# keyboard.net
KiCad netlist of a schematic drawn in EAGLE
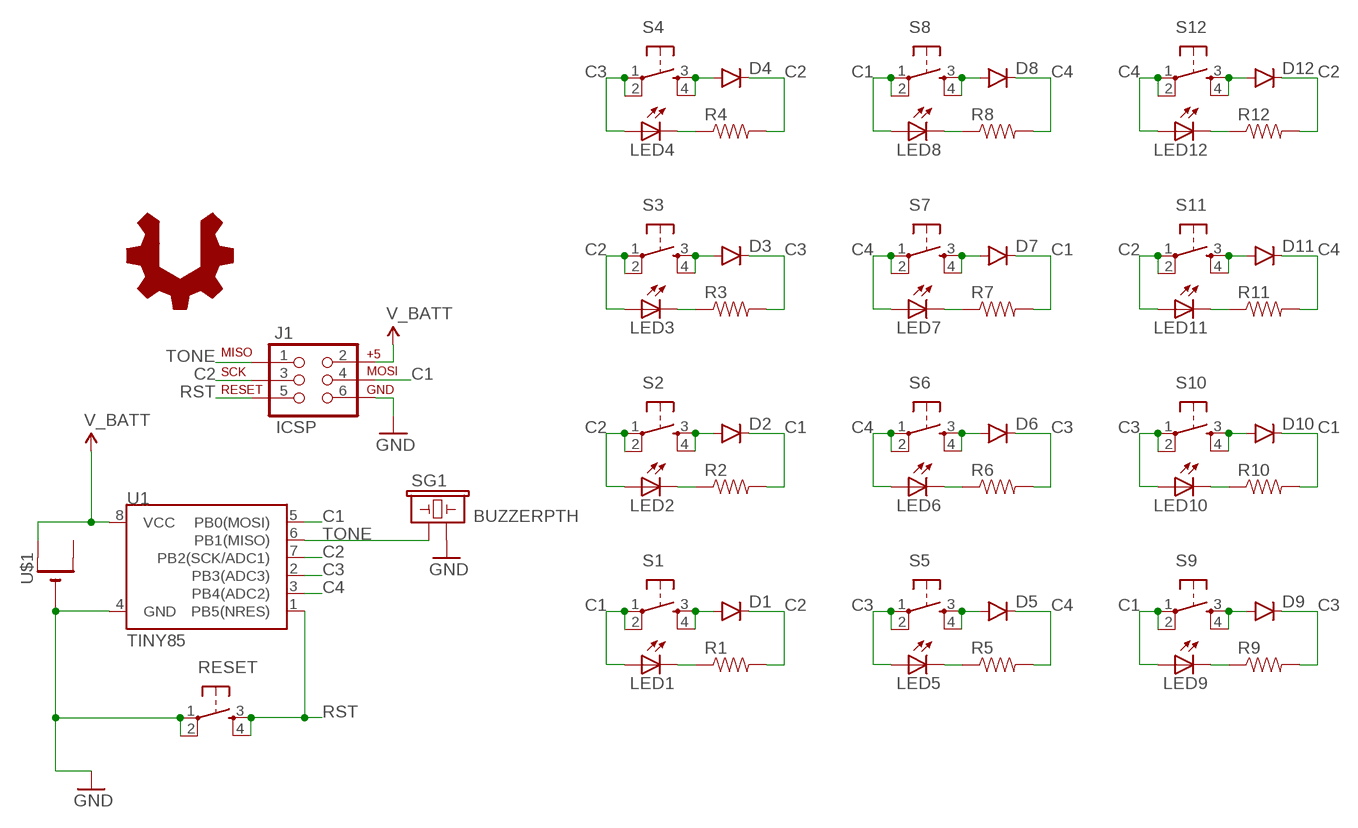
[diagram p0: schematic, sheet 1]

(export (version "E")
  (design (tool "Eeschema 10.0.6"))
  (components
    (comp (ref "D1")
      (value "DIODE1N4148")
      (footprint "eagle-import:DIODE-1N4148")
      (libsource (lib "eagle-import") (part "DIODE1N4148"))
    )
    (comp (ref "D2")
      (value "DIODE1N4148")
      (footprint "eagle-import:DIODE-1N4148")
      (libsource (lib "eagle-import") (part "DIODE1N4148"))
    )
    (comp (ref "D3")
      (value "DIODE1N4148")
      (footprint "eagle-import:DIODE-1N4148")
      (libsource (lib "eagle-import") (part "DIODE1N4148"))
    )
    (comp (ref "D4")
      (value "DIODE1N4148")
      (footprint "eagle-import:DIODE-1N4148")
      (libsource (lib "eagle-import") (part "DIODE1N4148"))
    )
    (comp (ref "D5")
      (value "DIODE1N4148")
      (footprint "eagle-import:DIODE-1N4148")
      (libsource (lib "eagle-import") (part "DIODE1N4148"))
    )
    (comp (ref "D6")
      (value "DIODE1N4148")
      (footprint "eagle-import:DIODE-1N4148")
      (libsource (lib "eagle-import") (part "DIODE1N4148"))
    )
    (comp (ref "D7")
      (value "DIODE1N4148")
      (footprint "eagle-import:DIODE-1N4148")
      (libsource (lib "eagle-import") (part "DIODE1N4148"))
    )
    (comp (ref "D8")
      (value "DIODE1N4148")
      (footprint "eagle-import:DIODE-1N4148")
      (libsource (lib "eagle-import") (part "DIODE1N4148"))
    )
    (comp (ref "D9")
      (value "DIODE1N4148")
      (footprint "eagle-import:DIODE-1N4148")
      (libsource (lib "eagle-import") (part "DIODE1N4148"))
    )
    (comp (ref "D10")
      (value "DIODE1N4148")
      (footprint "eagle-import:DIODE-1N4148")
      (libsource (lib "eagle-import") (part "DIODE1N4148"))
    )
    (comp (ref "D11")
      (value "DIODE1N4148")
      (footprint "eagle-import:DIODE-1N4148")
      (libsource (lib "eagle-import") (part "DIODE1N4148"))
    )
    (comp (ref "D12")
      (value "DIODE1N4148")
      (footprint "eagle-import:DIODE-1N4148")
      (libsource (lib "eagle-import") (part "DIODE1N4148"))
    )
    (comp (ref "J1")
      (value "ICSP")
      (footprint "eagle-import:2X3-NS")
      (libsource (lib "eagle-import") (part "AVR_SPI_PRG_6LABELED"))
    )
    (comp (ref "LED1")
      (value "LED5MM")
      (footprint "eagle-import:LED5MM")
      (libsource (lib "eagle-import") (part "LED5MM"))
    )
    (comp (ref "LED2")
      (value "LED5MM")
      (footprint "eagle-import:LED5MM")
      (libsource (lib "eagle-import") (part "LED5MM"))
    )
    (comp (ref "LED3")
      (value "LED5MM")
      (footprint "eagle-import:LED5MM")
      (libsource (lib "eagle-import") (part "LED5MM"))
    )
    (comp (ref "LED4")
      (value "LED5MM")
      (footprint "eagle-import:LED5MM")
      (libsource (lib "eagle-import") (part "LED5MM"))
    )
    (comp (ref "LED5")
      (value "LED5MM")
      (footprint "eagle-import:LED5MM")
      (libsource (lib "eagle-import") (part "LED5MM"))
    )
    (comp (ref "LED6")
      (value "LED5MM")
      (footprint "eagle-import:LED5MM")
      (libsource (lib "eagle-import") (part "LED5MM"))
    )
    (comp (ref "LED7")
      (value "LED5MM")
      (footprint "eagle-import:LED5MM")
      (libsource (lib "eagle-import") (part "LED5MM"))
    )
    (comp (ref "LED8")
      (value "LED5MM")
      (footprint "eagle-import:LED5MM")
      (libsource (lib "eagle-import") (part "LED5MM"))
    )
    (comp (ref "LED9")
      (value "LED5MM")
      (footprint "eagle-import:LED5MM")
      (libsource (lib "eagle-import") (part "LED5MM"))
    )
    (comp (ref "LED10")
      (value "LED5MM")
      (footprint "eagle-import:LED5MM")
      (libsource (lib "eagle-import") (part "LED5MM"))
    )
    (comp (ref "LED11")
      (value "LED5MM")
      (footprint "eagle-import:LED5MM")
      (libsource (lib "eagle-import") (part "LED5MM"))
    )
    (comp (ref "LED12")
      (value "LED5MM")
      (footprint "eagle-import:LED5MM")
      (libsource (lib "eagle-import") (part "LED5MM"))
    )
    (comp (ref "R1")
      (value "RESISTORAXIAL-0.3")
      (footprint "eagle-import:AXIAL-0.3")
      (libsource (lib "eagle-import") (part "RESISTORAXIAL-0.3"))
    )
    (comp (ref "R2")
      (value "RESISTORAXIAL-0.3")
      (footprint "eagle-import:AXIAL-0.3")
      (libsource (lib "eagle-import") (part "RESISTORAXIAL-0.3"))
    )
    (comp (ref "R3")
      (value "RESISTORAXIAL-0.3")
      (footprint "eagle-import:AXIAL-0.3")
      (libsource (lib "eagle-import") (part "RESISTORAXIAL-0.3"))
    )
    (comp (ref "R4")
      (value "RESISTORAXIAL-0.3")
      (footprint "eagle-import:AXIAL-0.3")
      (libsource (lib "eagle-import") (part "RESISTORAXIAL-0.3"))
    )
    (comp (ref "R5")
      (value "RESISTORAXIAL-0.3")
      (footprint "eagle-import:AXIAL-0.3")
      (libsource (lib "eagle-import") (part "RESISTORAXIAL-0.3"))
    )
    (comp (ref "R6")
      (value "RESISTORAXIAL-0.3")
      (footprint "eagle-import:AXIAL-0.3")
      (libsource (lib "eagle-import") (part "RESISTORAXIAL-0.3"))
    )
    (comp (ref "R7")
      (value "RESISTORAXIAL-0.3")
      (footprint "eagle-import:AXIAL-0.3")
      (libsource (lib "eagle-import") (part "RESISTORAXIAL-0.3"))
    )
    (comp (ref "R8")
      (value "RESISTORAXIAL-0.3")
      (footprint "eagle-import:AXIAL-0.3")
      (libsource (lib "eagle-import") (part "RESISTORAXIAL-0.3"))
    )
    (comp (ref "R9")
      (value "RESISTORAXIAL-0.3")
      (footprint "eagle-import:AXIAL-0.3")
      (libsource (lib "eagle-import") (part "RESISTORAXIAL-0.3"))
    )
    (comp (ref "R10")
      (value "RESISTORAXIAL-0.3")
      (footprint "eagle-import:AXIAL-0.3")
      (libsource (lib "eagle-import") (part "RESISTORAXIAL-0.3"))
    )
    (comp (ref "R11")
      (value "RESISTORAXIAL-0.3")
      (footprint "eagle-import:AXIAL-0.3")
      (libsource (lib "eagle-import") (part "RESISTORAXIAL-0.3"))
    )
    (comp (ref "R12")
      (value "RESISTORAXIAL-0.3")
      (footprint "eagle-import:AXIAL-0.3")
      (libsource (lib "eagle-import") (part "RESISTORAXIAL-0.3"))
    )
    (comp (ref "RESET")
      (value "TAC_SWITCHPTH")
      (footprint "eagle-import:TACTILE-PTH")
      (libsource (lib "eagle-import") (part "TAC_SWITCHPTH"))
    )
    (comp (ref "S1")
      (value "TAC_SWITCHPTH")
      (footprint "eagle-import:TACTILE-PTH")
      (libsource (lib "eagle-import") (part "TAC_SWITCHPTH"))
    )
    (comp (ref "S2")
      (value "TAC_SWITCHPTH")
      (footprint "eagle-import:TACTILE-PTH")
      (libsource (lib "eagle-import") (part "TAC_SWITCHPTH"))
    )
    (comp (ref "S3")
      (value "TAC_SWITCHPTH")
      (footprint "eagle-import:TACTILE-PTH")
      (libsource (lib "eagle-import") (part "TAC_SWITCHPTH"))
    )
    (comp (ref "S4")
      (value "TAC_SWITCHPTH")
      (footprint "eagle-import:TACTILE-PTH")
      (libsource (lib "eagle-import") (part "TAC_SWITCHPTH"))
    )
    (comp (ref "S5")
      (value "TAC_SWITCHPTH")
      (footprint "eagle-import:TACTILE-PTH")
      (libsource (lib "eagle-import") (part "TAC_SWITCHPTH"))
    )
    (comp (ref "S6")
      (value "TAC_SWITCHPTH")
      (footprint "eagle-import:TACTILE-PTH")
      (libsource (lib "eagle-import") (part "TAC_SWITCHPTH"))
    )
    (comp (ref "S7")
      (value "TAC_SWITCHPTH")
      (footprint "eagle-import:TACTILE-PTH")
      (libsource (lib "eagle-import") (part "TAC_SWITCHPTH"))
    )
    (comp (ref "S8")
      (value "TAC_SWITCHPTH")
      (footprint "eagle-import:TACTILE-PTH")
      (libsource (lib "eagle-import") (part "TAC_SWITCHPTH"))
    )
    (comp (ref "S9")
      (value "TAC_SWITCHPTH")
      (footprint "eagle-import:TACTILE-PTH")
      (libsource (lib "eagle-import") (part "TAC_SWITCHPTH"))
    )
    (comp (ref "S10")
      (value "TAC_SWITCHPTH")
      (footprint "eagle-import:TACTILE-PTH")
      (libsource (lib "eagle-import") (part "TAC_SWITCHPTH"))
    )
    (comp (ref "S11")
      (value "TAC_SWITCHPTH")
      (footprint "eagle-import:TACTILE-PTH")
      (libsource (lib "eagle-import") (part "TAC_SWITCHPTH"))
    )
    (comp (ref "S12")
      (value "TAC_SWITCHPTH")
      (footprint "eagle-import:TACTILE-PTH")
      (libsource (lib "eagle-import") (part "TAC_SWITCHPTH"))
    )
    (comp (ref "SG1")
      (value "BUZZERPTH")
      (footprint "eagle-import:BUZZER-12MM")
      (libsource (lib "eagle-import") (part "BUZZERPTH"))
    )
    (comp (ref "U$1")
      (value "CR2032THM")
      (footprint "eagle-import:CR2032-THRU")
      (libsource (lib "eagle-import") (part "CR2032THM"))
    )
    (comp (ref "U$2")
      (value "USER_HACKABLE")
      (footprint "eagle-import:USER_HACKABLE")
      (libsource (lib "eagle-import") (part "USER_HACKABLE"))
    )
    (comp (ref "U1")
      (value "TINY85")
      (footprint "eagle-import:DIP08")
      (libsource (lib "eagle-import") (part "ATTINY45TINY85-20-DIP"))
    )
  )
  (nets
    (net (code "1") (name "/C1") (class "Default")
      (node (ref "D10") (pin "C") (pinfunction "C_C") (pintype "passive"))
      (node (ref "D2") (pin "C") (pinfunction "C_C") (pintype "passive"))
      (node (ref "D7") (pin "C") (pinfunction "C_C") (pintype "passive"))
      (node (ref "J1") (pin "4") (pinfunction "MOSI_4") (pintype "passive"))
      (node (ref "LED1") (pin "A") (pinfunction "A_A") (pintype "passive"))
      (node (ref "LED8") (pin "A") (pinfunction "A_A") (pintype "passive"))
      (node (ref "LED9") (pin "A") (pinfunction "A_A") (pintype "passive"))
      (node (ref "R10") (pin "P$2") (pinfunction "2_P$2") (pintype "passive"))
      (node (ref "R2") (pin "P$2") (pinfunction "2_P$2") (pintype "passive"))
      (node (ref "R7") (pin "P$2") (pinfunction "2_P$2") (pintype "passive"))
      (node (ref "S1") (pin "1") (pinfunction "1_1") (pintype "passive"))
      (node (ref "S1") (pin "2") (pinfunction "2_2") (pintype "passive"))
      (node (ref "S8") (pin "1") (pinfunction "1_1") (pintype "passive"))
      (node (ref "S8") (pin "2") (pinfunction "2_2") (pintype "passive"))
      (node (ref "S9") (pin "1") (pinfunction "1_1") (pintype "passive"))
      (node (ref "S9") (pin "2") (pinfunction "2_2") (pintype "passive"))
      (node (ref "U1") (pin "5") (pinfunction "PB0(MOSI)_5") (pintype "bidirectional"))
    )
    (net (code "2") (name "/C2") (class "Default")
      (node (ref "D1") (pin "C") (pinfunction "C_C") (pintype "passive"))
      (node (ref "D12") (pin "C") (pinfunction "C_C") (pintype "passive"))
      (node (ref "D4") (pin "C") (pinfunction "C_C") (pintype "passive"))
      (node (ref "J1") (pin "3") (pinfunction "SCK_3") (pintype "passive"))
      (node (ref "LED11") (pin "A") (pinfunction "A_A") (pintype "passive"))
      (node (ref "LED2") (pin "A") (pinfunction "A_A") (pintype "passive"))
      (node (ref "LED3") (pin "A") (pinfunction "A_A") (pintype "passive"))
      (node (ref "R1") (pin "P$2") (pinfunction "2_P$2") (pintype "passive"))
      (node (ref "R12") (pin "P$2") (pinfunction "2_P$2") (pintype "passive"))
      (node (ref "R4") (pin "P$2") (pinfunction "2_P$2") (pintype "passive"))
      (node (ref "S11") (pin "1") (pinfunction "1_1") (pintype "passive"))
      (node (ref "S11") (pin "2") (pinfunction "2_2") (pintype "passive"))
      (node (ref "S2") (pin "1") (pinfunction "1_1") (pintype "passive"))
      (node (ref "S2") (pin "2") (pinfunction "2_2") (pintype "passive"))
      (node (ref "S3") (pin "1") (pinfunction "1_1") (pintype "passive"))
      (node (ref "S3") (pin "2") (pinfunction "2_2") (pintype "passive"))
      (node (ref "U1") (pin "7") (pinfunction "PB2(SCK/ADC1)_7") (pintype "bidirectional"))
    )
    (net (code "3") (name "/C3") (class "Default")
      (node (ref "D3") (pin "C") (pinfunction "C_C") (pintype "passive"))
      (node (ref "D6") (pin "C") (pinfunction "C_C") (pintype "passive"))
      (node (ref "D9") (pin "C") (pinfunction "C_C") (pintype "passive"))
      (node (ref "LED10") (pin "A") (pinfunction "A_A") (pintype "passive"))
      (node (ref "LED4") (pin "A") (pinfunction "A_A") (pintype "passive"))
      (node (ref "LED5") (pin "A") (pinfunction "A_A") (pintype "passive"))
      (node (ref "R3") (pin "P$2") (pinfunction "2_P$2") (pintype "passive"))
      (node (ref "R6") (pin "P$2") (pinfunction "2_P$2") (pintype "passive"))
      (node (ref "R9") (pin "P$2") (pinfunction "2_P$2") (pintype "passive"))
      (node (ref "S10") (pin "1") (pinfunction "1_1") (pintype "passive"))
      (node (ref "S10") (pin "2") (pinfunction "2_2") (pintype "passive"))
      (node (ref "S4") (pin "1") (pinfunction "1_1") (pintype "passive"))
      (node (ref "S4") (pin "2") (pinfunction "2_2") (pintype "passive"))
      (node (ref "S5") (pin "1") (pinfunction "1_1") (pintype "passive"))
      (node (ref "S5") (pin "2") (pinfunction "2_2") (pintype "passive"))
      (node (ref "U1") (pin "2") (pinfunction "PB3(ADC3)_2") (pintype "bidirectional"))
    )
    (net (code "4") (name "/C4") (class "Default")
      (node (ref "D11") (pin "C") (pinfunction "C_C") (pintype "passive"))
      (node (ref "D5") (pin "C") (pinfunction "C_C") (pintype "passive"))
      (node (ref "D8") (pin "C") (pinfunction "C_C") (pintype "passive"))
      (node (ref "LED12") (pin "A") (pinfunction "A_A") (pintype "passive"))
      (node (ref "LED6") (pin "A") (pinfunction "A_A") (pintype "passive"))
      (node (ref "LED7") (pin "A") (pinfunction "A_A") (pintype "passive"))
      (node (ref "R11") (pin "P$2") (pinfunction "2_P$2") (pintype "passive"))
      (node (ref "R5") (pin "P$2") (pinfunction "2_P$2") (pintype "passive"))
      (node (ref "R8") (pin "P$2") (pinfunction "2_P$2") (pintype "passive"))
      (node (ref "S12") (pin "1") (pinfunction "1_1") (pintype "passive"))
      (node (ref "S12") (pin "2") (pinfunction "2_2") (pintype "passive"))
      (node (ref "S6") (pin "1") (pinfunction "1_1") (pintype "passive"))
      (node (ref "S6") (pin "2") (pinfunction "2_2") (pintype "passive"))
      (node (ref "S7") (pin "1") (pinfunction "1_1") (pintype "passive"))
      (node (ref "S7") (pin "2") (pinfunction "2_2") (pintype "passive"))
      (node (ref "U1") (pin "3") (pinfunction "PB4(ADC2)_3") (pintype "bidirectional"))
    )
    (net (code "5") (name "/RST") (class "Default")
      (node (ref "J1") (pin "5") (pinfunction "RST_5") (pintype "passive"))
      (node (ref "RESET") (pin "3") (pinfunction "3_3") (pintype "passive"))
      (node (ref "RESET") (pin "4") (pinfunction "4_4") (pintype "passive"))
      (node (ref "U1") (pin "1") (pinfunction "PB5(NRES)_1") (pintype "bidirectional"))
    )
    (net (code "6") (name "/TONE") (class "Default")
      (node (ref "J1") (pin "1") (pinfunction "MISO_1") (pintype "passive"))
      (node (ref "SG1") (pin "+") (pinfunction "1_+") (pintype "passive"))
      (node (ref "U1") (pin "6") (pinfunction "PB1(MISO)_6") (pintype "bidirectional"))
    )
    (net (code "7") (name "GND") (class "Default")
      (node (ref "J1") (pin "6") (pinfunction "GND_6") (pintype "passive"))
      (node (ref "RESET") (pin "1") (pinfunction "1_1") (pintype "passive"))
      (node (ref "RESET") (pin "2") (pinfunction "2_2") (pintype "passive"))
      (node (ref "SG1") (pin "-") (pinfunction "2_-") (pintype "passive"))
      (node (ref "U$1") (pin "-") (pinfunction "-_-") (pintype "passive"))
      (node (ref "U1") (pin "4") (pinfunction "GND_4") (pintype "bidirectional"))
    )
    (net (code "8") (name "Net-(D1-PadA)") (class "Default")
      (node (ref "D1") (pin "A") (pinfunction "A_A") (pintype "passive"))
      (node (ref "S1") (pin "3") (pinfunction "3_3") (pintype "passive"))
      (node (ref "S1") (pin "4") (pinfunction "4_4") (pintype "passive"))
    )
    (net (code "9") (name "Net-(D2-PadA)") (class "Default")
      (node (ref "D2") (pin "A") (pinfunction "A_A") (pintype "passive"))
      (node (ref "S2") (pin "3") (pinfunction "3_3") (pintype "passive"))
      (node (ref "S2") (pin "4") (pinfunction "4_4") (pintype "passive"))
    )
    (net (code "10") (name "Net-(D3-PadA)") (class "Default")
      (node (ref "D3") (pin "A") (pinfunction "A_A") (pintype "passive"))
      (node (ref "S3") (pin "3") (pinfunction "3_3") (pintype "passive"))
      (node (ref "S3") (pin "4") (pinfunction "4_4") (pintype "passive"))
    )
    (net (code "11") (name "Net-(D4-PadA)") (class "Default")
      (node (ref "D4") (pin "A") (pinfunction "A_A") (pintype "passive"))
      (node (ref "S4") (pin "3") (pinfunction "3_3") (pintype "passive"))
      (node (ref "S4") (pin "4") (pinfunction "4_4") (pintype "passive"))
    )
    (net (code "12") (name "Net-(D5-PadA)") (class "Default")
      (node (ref "D5") (pin "A") (pinfunction "A_A") (pintype "passive"))
      (node (ref "S5") (pin "3") (pinfunction "3_3") (pintype "passive"))
      (node (ref "S5") (pin "4") (pinfunction "4_4") (pintype "passive"))
    )
    (net (code "13") (name "Net-(D6-PadA)") (class "Default")
      (node (ref "D6") (pin "A") (pinfunction "A_A") (pintype "passive"))
      (node (ref "S6") (pin "3") (pinfunction "3_3") (pintype "passive"))
      (node (ref "S6") (pin "4") (pinfunction "4_4") (pintype "passive"))
    )
    (net (code "14") (name "Net-(D7-PadA)") (class "Default")
      (node (ref "D7") (pin "A") (pinfunction "A_A") (pintype "passive"))
      (node (ref "S7") (pin "3") (pinfunction "3_3") (pintype "passive"))
      (node (ref "S7") (pin "4") (pinfunction "4_4") (pintype "passive"))
    )
    (net (code "15") (name "Net-(D8-PadA)") (class "Default")
      (node (ref "D8") (pin "A") (pinfunction "A_A") (pintype "passive"))
      (node (ref "S8") (pin "3") (pinfunction "3_3") (pintype "passive"))
      (node (ref "S8") (pin "4") (pinfunction "4_4") (pintype "passive"))
    )
    (net (code "16") (name "Net-(D9-PadA)") (class "Default")
      (node (ref "D9") (pin "A") (pinfunction "A_A") (pintype "passive"))
      (node (ref "S9") (pin "3") (pinfunction "3_3") (pintype "passive"))
      (node (ref "S9") (pin "4") (pinfunction "4_4") (pintype "passive"))
    )
    (net (code "17") (name "Net-(D10-PadA)") (class "Default")
      (node (ref "D10") (pin "A") (pinfunction "A_A") (pintype "passive"))
      (node (ref "S10") (pin "3") (pinfunction "3_3") (pintype "passive"))
      (node (ref "S10") (pin "4") (pinfunction "4_4") (pintype "passive"))
    )
    (net (code "18") (name "Net-(D11-PadA)") (class "Default")
      (node (ref "D11") (pin "A") (pinfunction "A_A") (pintype "passive"))
      (node (ref "S11") (pin "3") (pinfunction "3_3") (pintype "passive"))
      (node (ref "S11") (pin "4") (pinfunction "4_4") (pintype "passive"))
    )
    (net (code "19") (name "Net-(D12-PadA)") (class "Default")
      (node (ref "D12") (pin "A") (pinfunction "A_A") (pintype "passive"))
      (node (ref "S12") (pin "3") (pinfunction "3_3") (pintype "passive"))
      (node (ref "S12") (pin "4") (pinfunction "4_4") (pintype "passive"))
    )
    (net (code "20") (name "Net-(LED1-C)") (class "Default")
      (node (ref "LED1") (pin "K") (pinfunction "C_K") (pintype "passive"))
      (node (ref "R1") (pin "P$1") (pinfunction "1_P$1") (pintype "passive"))
    )
    (net (code "21") (name "Net-(LED2-C)") (class "Default")
      (node (ref "LED2") (pin "K") (pinfunction "C_K") (pintype "passive"))
      (node (ref "R2") (pin "P$1") (pinfunction "1_P$1") (pintype "passive"))
    )
    (net (code "22") (name "Net-(LED3-C)") (class "Default")
      (node (ref "LED3") (pin "K") (pinfunction "C_K") (pintype "passive"))
      (node (ref "R3") (pin "P$1") (pinfunction "1_P$1") (pintype "passive"))
    )
    (net (code "23") (name "Net-(LED4-C)") (class "Default")
      (node (ref "LED4") (pin "K") (pinfunction "C_K") (pintype "passive"))
      (node (ref "R4") (pin "P$1") (pinfunction "1_P$1") (pintype "passive"))
    )
    (net (code "24") (name "Net-(LED5-C)") (class "Default")
      (node (ref "LED5") (pin "K") (pinfunction "C_K") (pintype "passive"))
      (node (ref "R5") (pin "P$1") (pinfunction "1_P$1") (pintype "passive"))
    )
    (net (code "25") (name "Net-(LED6-C)") (class "Default")
      (node (ref "LED6") (pin "K") (pinfunction "C_K") (pintype "passive"))
      (node (ref "R6") (pin "P$1") (pinfunction "1_P$1") (pintype "passive"))
    )
    (net (code "26") (name "Net-(LED7-C)") (class "Default")
      (node (ref "LED7") (pin "K") (pinfunction "C_K") (pintype "passive"))
      (node (ref "R7") (pin "P$1") (pinfunction "1_P$1") (pintype "passive"))
    )
    (net (code "27") (name "Net-(LED8-C)") (class "Default")
      (node (ref "LED8") (pin "K") (pinfunction "C_K") (pintype "passive"))
      (node (ref "R8") (pin "P$1") (pinfunction "1_P$1") (pintype "passive"))
    )
    (net (code "28") (name "Net-(LED9-C)") (class "Default")
      (node (ref "LED9") (pin "K") (pinfunction "C_K") (pintype "passive"))
      (node (ref "R9") (pin "P$1") (pinfunction "1_P$1") (pintype "passive"))
    )
    (net (code "29") (name "Net-(LED10-C)") (class "Default")
      (node (ref "LED10") (pin "K") (pinfunction "C_K") (pintype "passive"))
      (node (ref "R10") (pin "P$1") (pinfunction "1_P$1") (pintype "passive"))
    )
    (net (code "30") (name "Net-(LED11-C)") (class "Default")
      (node (ref "LED11") (pin "K") (pinfunction "C_K") (pintype "passive"))
      (node (ref "R11") (pin "P$1") (pinfunction "1_P$1") (pintype "passive"))
    )
    (net (code "31") (name "Net-(LED12-C)") (class "Default")
      (node (ref "LED12") (pin "K") (pinfunction "C_K") (pintype "passive"))
      (node (ref "R12") (pin "P$1") (pinfunction "1_P$1") (pintype "passive"))
    )
    (net (code "32") (name "V_BATT") (class "Default")
      (node (ref "J1") (pin "2") (pinfunction "V+_2") (pintype "passive"))
      (node (ref "U$1") (pin "+1") (pinfunction "+_+1") (pintype "passive"))
      (node (ref "U1") (pin "8") (pinfunction "VCC_8") (pintype "bidirectional"))
    )
    (net (code "33") (name "unconnected-(U$1-+1-Pad+2)") (class "Default")
      (node (ref "U$1") (pin "+2") (pinfunction "+1_+2") (pintype "passive"))
    )
  )
)
